# Layer2_v1_1.net
KiCad netlist of a schematic drawn in EAGLE
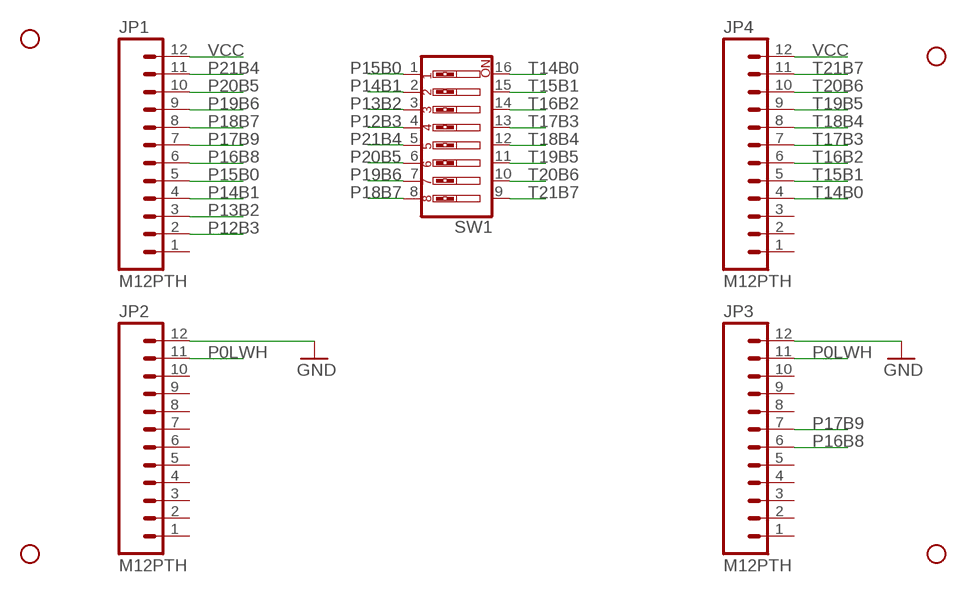
[diagram p0: schematic, sheet 1]

(export (version "E")
  (design (tool "Eeschema 10.0.6"))
  (components
    (comp (ref "JP1")
      (value "M12PTH")
      (footprint "eagle-import:1X12")
      (libsource (lib "eagle-import") (part "M12PTH"))
    )
    (comp (ref "JP2")
      (value "M12PTH")
      (footprint "eagle-import:1X12")
      (libsource (lib "eagle-import") (part "M12PTH"))
    )
    (comp (ref "JP3")
      (value "M12PTH")
      (footprint "eagle-import:1X12")
      (libsource (lib "eagle-import") (part "M12PTH"))
    )
    (comp (ref "JP4")
      (value "M12PTH")
      (footprint "eagle-import:1X12")
      (libsource (lib "eagle-import") (part "M12PTH"))
    )
    (comp (ref "JP5")
      (value "STAND-OFF")
      (footprint "eagle-import:STAND-OFF")
      (libsource (lib "eagle-import") (part "STAND-OFF"))
    )
    (comp (ref "JP6")
      (value "STAND-OFF")
      (footprint "eagle-import:STAND-OFF")
      (libsource (lib "eagle-import") (part "STAND-OFF"))
    )
    (comp (ref "JP7")
      (value "STAND-OFF")
      (footprint "eagle-import:STAND-OFF")
      (libsource (lib "eagle-import") (part "STAND-OFF"))
    )
    (comp (ref "JP8")
      (value "STAND-OFF")
      (footprint "eagle-import:STAND-OFF")
      (libsource (lib "eagle-import") (part "STAND-OFF"))
    )
    (comp (ref "SW1")
      (value "SW_DIP-8")
      (footprint "eagle-import:DIPSWITCH-08")
      (libsource (lib "eagle-import") (part "SW_DIP-8"))
    )
  )
  (nets
    (net (code "1") (name "/P0LWH") (class "Default")
      (node (ref "JP2") (pin "11") (pinfunction "11_11") (pintype "passive"))
      (node (ref "JP3") (pin "11") (pinfunction "11_11") (pintype "passive"))
    )
    (net (code "2") (name "/P12B3") (class "Default")
      (node (ref "JP1") (pin "2") (pinfunction "2_2") (pintype "passive"))
      (node (ref "SW1") (pin "4") (pinfunction "4_4") (pintype "passive"))
    )
    (net (code "3") (name "/P13B2") (class "Default")
      (node (ref "JP1") (pin "3") (pinfunction "3_3") (pintype "passive"))
      (node (ref "SW1") (pin "3") (pinfunction "3_3") (pintype "passive"))
    )
    (net (code "4") (name "/P14B1") (class "Default")
      (node (ref "JP1") (pin "4") (pinfunction "4_4") (pintype "passive"))
      (node (ref "SW1") (pin "2") (pinfunction "2_2") (pintype "passive"))
    )
    (net (code "5") (name "/P15B0") (class "Default")
      (node (ref "JP1") (pin "5") (pinfunction "5_5") (pintype "passive"))
      (node (ref "SW1") (pin "1") (pinfunction "1_1") (pintype "passive"))
    )
    (net (code "6") (name "/P16B8") (class "Default")
      (node (ref "JP1") (pin "6") (pinfunction "6_6") (pintype "passive"))
      (node (ref "JP3") (pin "6") (pinfunction "6_6") (pintype "passive"))
    )
    (net (code "7") (name "/P17B9") (class "Default")
      (node (ref "JP1") (pin "7") (pinfunction "7_7") (pintype "passive"))
      (node (ref "JP3") (pin "7") (pinfunction "7_7") (pintype "passive"))
    )
    (net (code "8") (name "/P18B7") (class "Default")
      (node (ref "JP1") (pin "8") (pinfunction "8_8") (pintype "passive"))
      (node (ref "SW1") (pin "8") (pinfunction "8_8") (pintype "passive"))
    )
    (net (code "9") (name "/P19B6") (class "Default")
      (node (ref "JP1") (pin "9") (pinfunction "9_9") (pintype "passive"))
      (node (ref "SW1") (pin "7") (pinfunction "7_7") (pintype "passive"))
    )
    (net (code "10") (name "/P20B5") (class "Default")
      (node (ref "JP1") (pin "10") (pinfunction "10_10") (pintype "passive"))
      (node (ref "SW1") (pin "6") (pinfunction "6_6") (pintype "passive"))
    )
    (net (code "11") (name "/P21B4") (class "Default")
      (node (ref "JP1") (pin "11") (pinfunction "11_11") (pintype "passive"))
      (node (ref "SW1") (pin "5") (pinfunction "5_5") (pintype "passive"))
    )
    (net (code "12") (name "/T14B0") (class "Default")
      (node (ref "JP4") (pin "4") (pinfunction "4_4") (pintype "passive"))
      (node (ref "SW1") (pin "16") (pinfunction "16_16") (pintype "passive"))
    )
    (net (code "13") (name "/T15B1") (class "Default")
      (node (ref "JP4") (pin "5") (pinfunction "5_5") (pintype "passive"))
      (node (ref "SW1") (pin "15") (pinfunction "15_15") (pintype "passive"))
    )
    (net (code "14") (name "/T16B2") (class "Default")
      (node (ref "JP4") (pin "6") (pinfunction "6_6") (pintype "passive"))
      (node (ref "SW1") (pin "14") (pinfunction "14_14") (pintype "passive"))
    )
    (net (code "15") (name "/T17B3") (class "Default")
      (node (ref "JP4") (pin "7") (pinfunction "7_7") (pintype "passive"))
      (node (ref "SW1") (pin "13") (pinfunction "13_13") (pintype "passive"))
    )
    (net (code "16") (name "/T18B4") (class "Default")
      (node (ref "JP4") (pin "8") (pinfunction "8_8") (pintype "passive"))
      (node (ref "SW1") (pin "12") (pinfunction "12_12") (pintype "passive"))
    )
    (net (code "17") (name "/T19B5") (class "Default")
      (node (ref "JP4") (pin "9") (pinfunction "9_9") (pintype "passive"))
      (node (ref "SW1") (pin "11") (pinfunction "11_11") (pintype "passive"))
    )
    (net (code "18") (name "/T20B6") (class "Default")
      (node (ref "JP4") (pin "10") (pinfunction "10_10") (pintype "passive"))
      (node (ref "SW1") (pin "10") (pinfunction "10_10") (pintype "passive"))
    )
    (net (code "19") (name "/T21B7") (class "Default")
      (node (ref "JP4") (pin "11") (pinfunction "11_11") (pintype "passive"))
      (node (ref "SW1") (pin "9") (pinfunction "9_9") (pintype "passive"))
    )
    (net (code "20") (name "/VCC") (class "Default")
      (node (ref "JP1") (pin "12") (pinfunction "12_12") (pintype "passive"))
      (node (ref "JP4") (pin "12") (pinfunction "12_12") (pintype "passive"))
    )
    (net (code "21") (name "GND") (class "Default")
      (node (ref "JP2") (pin "12") (pinfunction "12_12") (pintype "passive"))
      (node (ref "JP3") (pin "12") (pinfunction "12_12") (pintype "passive"))
    )
    (net (code "22") (name "unconnected-(JP1-Pad1)") (class "Default")
      (node (ref "JP1") (pin "1") (pinfunction "1_1") (pintype "passive"))
    )
    (net (code "23") (name "unconnected-(JP2-Pad1)") (class "Default")
      (node (ref "JP2") (pin "1") (pinfunction "1_1") (pintype "passive"))
    )
    (net (code "24") (name "unconnected-(JP2-Pad2)") (class "Default")
      (node (ref "JP2") (pin "2") (pinfunction "2_2") (pintype "passive"))
    )
    (net (code "25") (name "unconnected-(JP2-Pad3)") (class "Default")
      (node (ref "JP2") (pin "3") (pinfunction "3_3") (pintype "passive"))
    )
    (net (code "26") (name "unconnected-(JP2-Pad4)") (class "Default")
      (node (ref "JP2") (pin "4") (pinfunction "4_4") (pintype "passive"))
    )
    (net (code "27") (name "unconnected-(JP2-Pad5)") (class "Default")
      (node (ref "JP2") (pin "5") (pinfunction "5_5") (pintype "passive"))
    )
    (net (code "28") (name "unconnected-(JP2-Pad6)") (class "Default")
      (node (ref "JP2") (pin "6") (pinfunction "6_6") (pintype "passive"))
    )
    (net (code "29") (name "unconnected-(JP2-Pad7)") (class "Default")
      (node (ref "JP2") (pin "7") (pinfunction "7_7") (pintype "passive"))
    )
    (net (code "30") (name "unconnected-(JP2-Pad8)") (class "Default")
      (node (ref "JP2") (pin "8") (pinfunction "8_8") (pintype "passive"))
    )
    (net (code "31") (name "unconnected-(JP2-Pad9)") (class "Default")
      (node (ref "JP2") (pin "9") (pinfunction "9_9") (pintype "passive"))
    )
    (net (code "32") (name "unconnected-(JP2-Pad10)") (class "Default")
      (node (ref "JP2") (pin "10") (pinfunction "10_10") (pintype "passive"))
    )
    (net (code "33") (name "unconnected-(JP3-Pad1)") (class "Default")
      (node (ref "JP3") (pin "1") (pinfunction "1_1") (pintype "passive"))
    )
    (net (code "34") (name "unconnected-(JP3-Pad2)") (class "Default")
      (node (ref "JP3") (pin "2") (pinfunction "2_2") (pintype "passive"))
    )
    (net (code "35") (name "unconnected-(JP3-Pad3)") (class "Default")
      (node (ref "JP3") (pin "3") (pinfunction "3_3") (pintype "passive"))
    )
    (net (code "36") (name "unconnected-(JP3-Pad4)") (class "Default")
      (node (ref "JP3") (pin "4") (pinfunction "4_4") (pintype "passive"))
    )
    (net (code "37") (name "unconnected-(JP3-Pad5)") (class "Default")
      (node (ref "JP3") (pin "5") (pinfunction "5_5") (pintype "passive"))
    )
    (net (code "38") (name "unconnected-(JP3-Pad8)") (class "Default")
      (node (ref "JP3") (pin "8") (pinfunction "8_8") (pintype "passive"))
    )
    (net (code "39") (name "unconnected-(JP3-Pad9)") (class "Default")
      (node (ref "JP3") (pin "9") (pinfunction "9_9") (pintype "passive"))
    )
    (net (code "40") (name "unconnected-(JP3-Pad10)") (class "Default")
      (node (ref "JP3") (pin "10") (pinfunction "10_10") (pintype "passive"))
    )
    (net (code "41") (name "unconnected-(JP4-Pad1)") (class "Default")
      (node (ref "JP4") (pin "1") (pinfunction "1_1") (pintype "passive"))
    )
    (net (code "42") (name "unconnected-(JP4-Pad2)") (class "Default")
      (node (ref "JP4") (pin "2") (pinfunction "2_2") (pintype "passive"))
    )
    (net (code "43") (name "unconnected-(JP4-Pad3)") (class "Default")
      (node (ref "JP4") (pin "3") (pinfunction "3_3") (pintype "passive"))
    )
  )
)
